# 2_ADC.net
KiCad netlist of a schematic drawn in Altium Designer
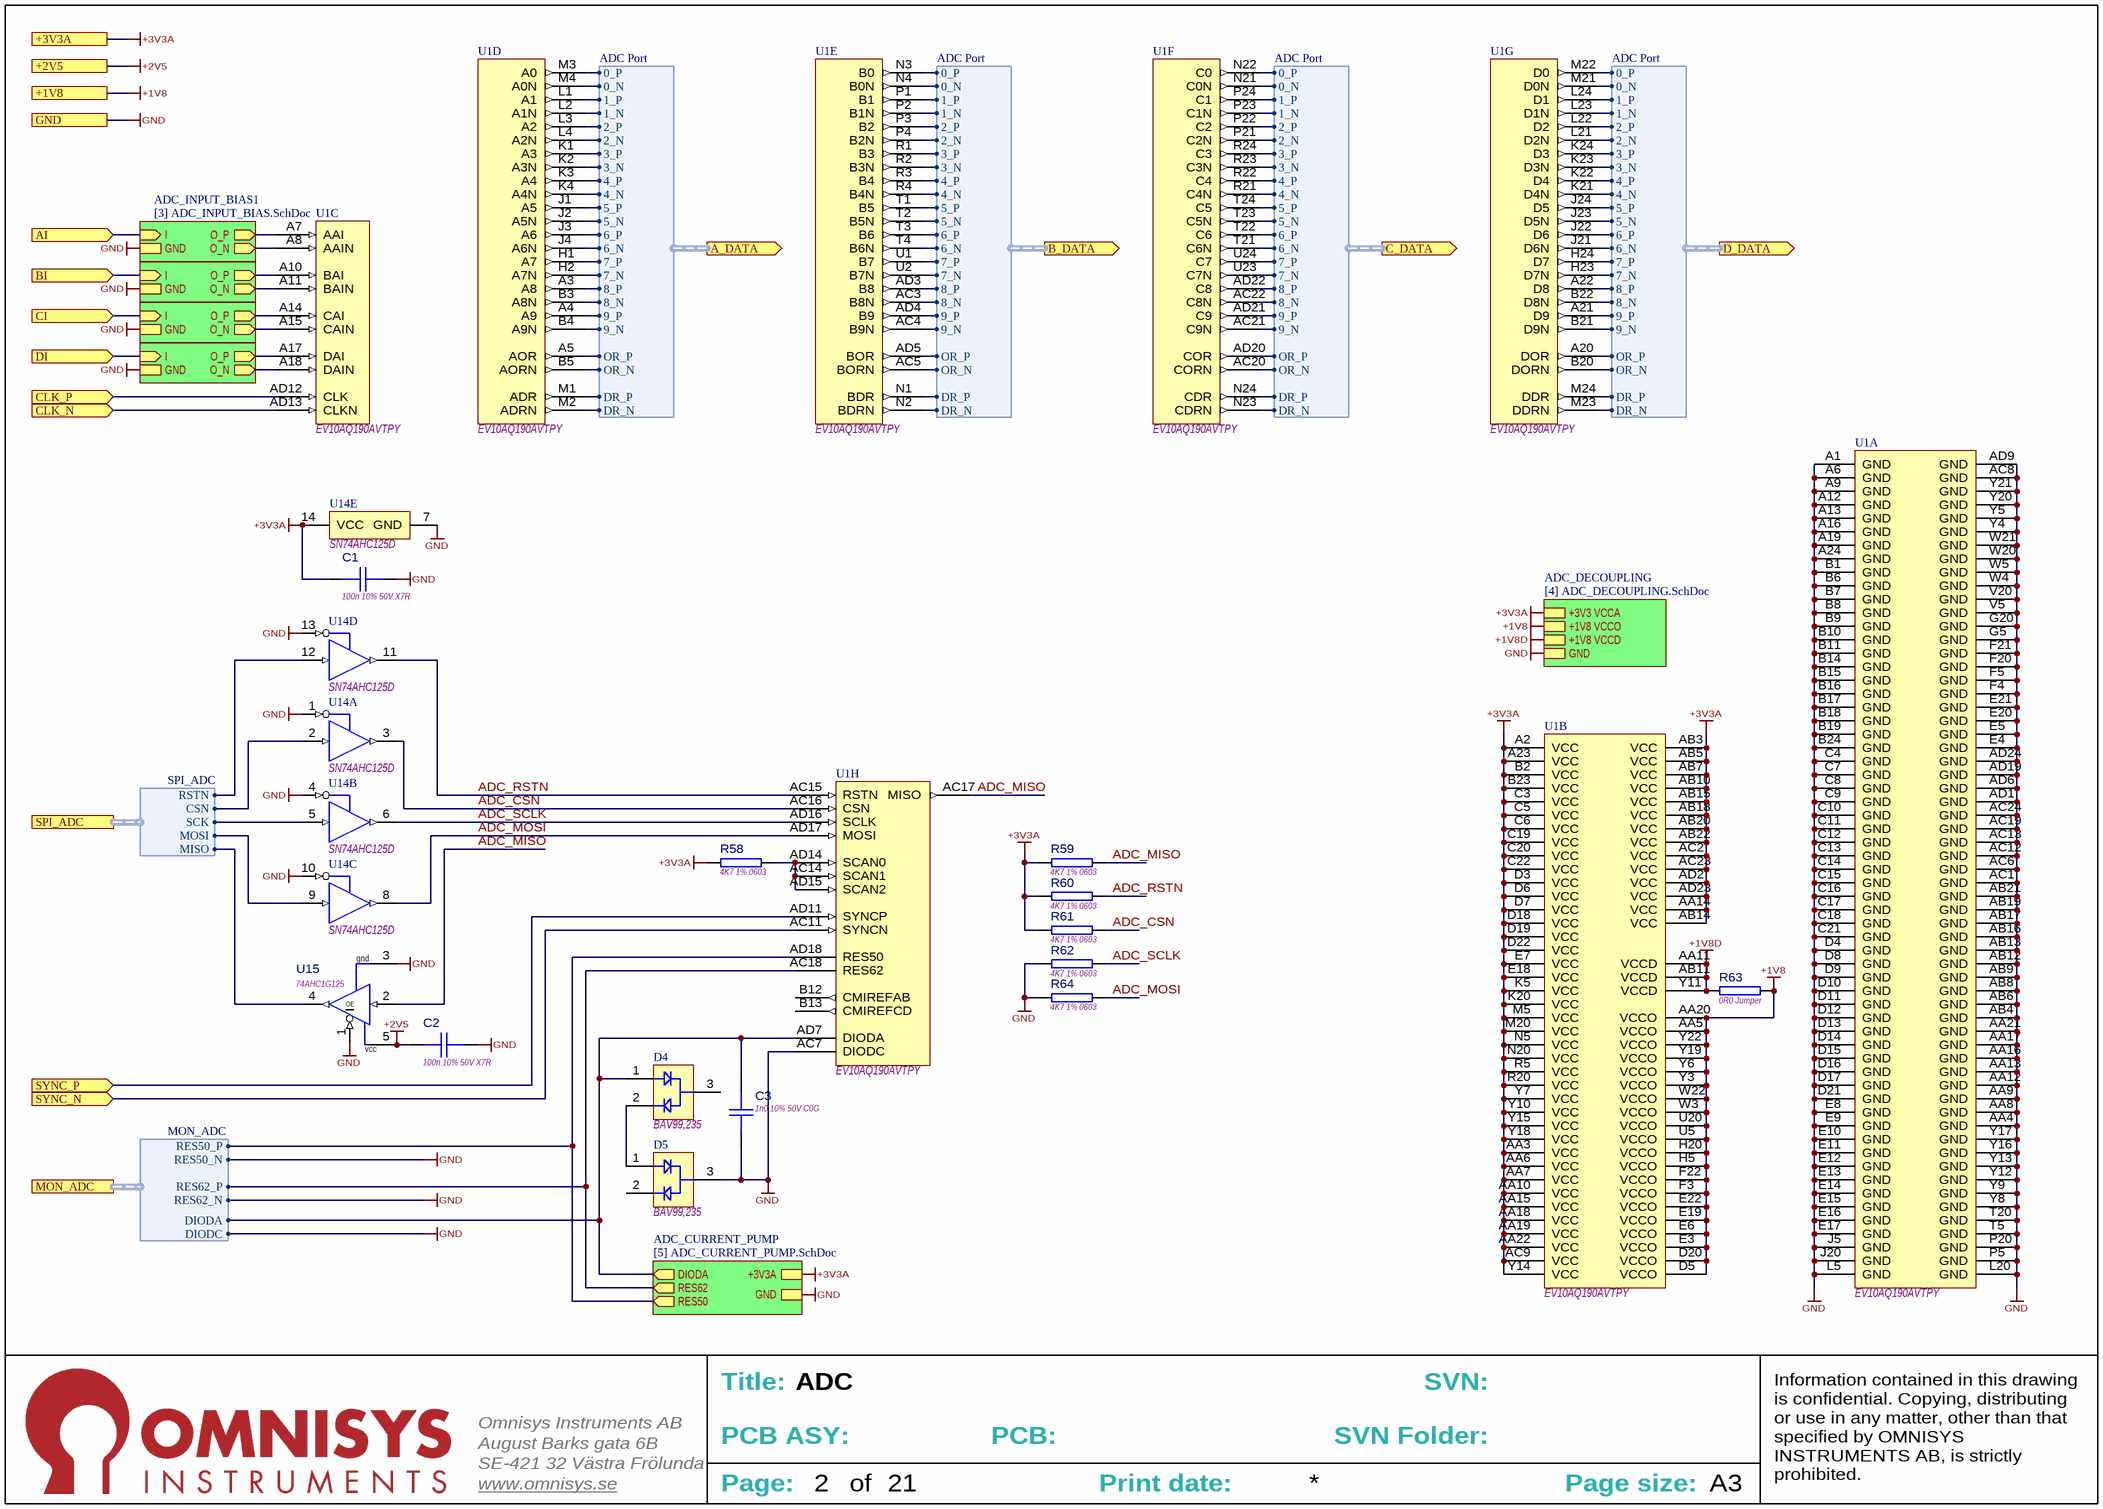
[diagram p0: [2] ADC.SchDoc]

(export (version "E")
  (design (tool "Eeschema 10.0.6"))
  (components
    (comp (ref "C1")
      (value "100n 10% 50V X7R")
      (footprint "CAPC1608X90N")
      (description "Ceramic Chip Capacitor, 0603/1608")
      (fields (field (name "TOLERANCE") "10%"))
      (libsource (lib "Omnisys Vault") (part "CAP-2PIN"))
    )
    (comp (ref "C2")
      (value "100n 10% 50V X7R")
      (footprint "CAPC1608X90N")
      (description "Ceramic Chip Capacitor, 0603/1608")
      (fields (field (name "TOLERANCE") "10%"))
      (libsource (lib "Omnisys Vault") (part "CAP-2PIN"))
    )
    (comp (ref "C3")
      (value "1n0 10% 50V C0G")
      (footprint "CAPC1608X90N")
      (description "Ceramic Chip Capacitor, 0603/1608")
      (fields (field (name "TOLERANCE") "5%"))
      (libsource (lib "Omnisys Vault") (part "CAP-2PIN"))
    )
    (comp (ref "D4")
      (value "BAV99,235")
      (footprint "SOT95P230X110-3N")
      (description "BAV99 Series 100 V 215 mA SMT High Speed Switching Diode - SOT-23")
      (fields (field (name "VOLTAGE") "75V"))
      (libsource (lib "Omnisys Vault") (part "INF-D_A1K2C3-3"))
    )
    (comp (ref "D5")
      (value "BAV99,235")
      (footprint "SOT95P230X110-3N")
      (description "BAV99 Series 100 V 215 mA SMT High Speed Switching Diode - SOT-23")
      (fields (field (name "VOLTAGE") "75V"))
      (libsource (lib "Omnisys Vault") (part "INF-D_A1K2C3-3"))
    )
    (comp (ref "R58")
      (value "4K7 1% 0603")
      (footprint "RESC1608N")
      (description "Thick film Chip Resistor, 0603/1608")
      (fields (field (name "POWER") "100mW") (field (name "TOLERANCE") "1%"))
      (libsource (lib "Omnisys Vault") (part "RES-2PIN"))
    )
    (comp (ref "R59")
      (value "4K7 1% 0603")
      (footprint "RESC1608N")
      (description "Thick film Chip Resistor, 0603/1608")
      (fields (field (name "POWER") "100mW") (field (name "TOLERANCE") "1%"))
      (libsource (lib "Omnisys Vault") (part "RES-2PIN"))
    )
    (comp (ref "R60")
      (value "4K7 1% 0603")
      (footprint "RESC1608N")
      (description "Thick film Chip Resistor, 0603/1608")
      (fields (field (name "POWER") "100mW") (field (name "TOLERANCE") "1%"))
      (libsource (lib "Omnisys Vault") (part "RES-2PIN"))
    )
    (comp (ref "R61")
      (value "4K7 1% 0603")
      (footprint "RESC1608N")
      (description "Thick film Chip Resistor, 0603/1608")
      (fields (field (name "POWER") "100mW") (field (name "TOLERANCE") "1%"))
      (libsource (lib "Omnisys Vault") (part "RES-2PIN"))
    )
    (comp (ref "R62")
      (value "4K7 1% 0603")
      (footprint "RESC1608N")
      (description "Thick film Chip Resistor, 0603/1608")
      (fields (field (name "POWER") "100mW") (field (name "TOLERANCE") "1%"))
      (libsource (lib "Omnisys Vault") (part "RES-2PIN"))
    )
    (comp (ref "R63")
      (value "0R0 Jumper")
      (footprint "RESC2012N")
      (description "Thick film Chip Resistor, 0805/2012")
      (fields (field (name "POWER") "0W") (field (name "TOLERANCE") "0%"))
      (libsource (lib "Omnisys Vault") (part "RES-2PIN"))
    )
    (comp (ref "R64")
      (value "4K7 1% 0603")
      (footprint "RESC1608N")
      (description "Thick film Chip Resistor, 0603/1608")
      (fields (field (name "POWER") "100mW") (field (name "TOLERANCE") "1%"))
      (libsource (lib "Omnisys Vault") (part "RES-2PIN"))
    )
    (comp (ref "U1")
      (value "EV10AQ190AVTPY")
      (footprint "BGA380C127P24X24_3100X3100X160")
      (description "Quad ADC 1.25Gsps 10-bit Parallel/LVDS 380-Pin EBGA")
      (libsource (lib "Omnisys Vault") (part "EV10AQ190AVTPY"))
    )
    (comp (ref "U14")
      (value "SN74AHC125D")
      (footprint "SOIC127P600X175-14N")
      (description "Buffer/Line Driver 4-CH Non-Inverting 3-ST CMOS 14-Pin SOIC Tube")
      (libsource (lib "Omnisys Vault") (part "SN74AHC125D"))
    )
    (comp (ref "U15")
      (value "74AHC1G125")
      (footprint "SOT95P280X100-5N")
      (description "Single bus buffer gate with 3-state output")
      (libsource (lib "Omnisys Vault") (part "74AHC1G125"))
    )
  )
  (nets
    (net (code "5") (name "+1V8") (class "Default")
      (node (ref "R63") (pin "2") (pinfunction "2_2") (pintype "passive"))
      (node (ref "U1") (pin "AA20") (pinfunction "VCCO_AA20") (pintype "power_in"))
      (node (ref "U1") (pin "AA5") (pinfunction "VCCO_AA5") (pintype "power_in"))
      (node (ref "U1") (pin "D20") (pinfunction "VCCO_D20") (pintype "power_in"))
      (node (ref "U1") (pin "D5") (pinfunction "VCCO_D5") (pintype "power_in"))
      (node (ref "U1") (pin "E19") (pinfunction "VCCO_E19") (pintype "power_in"))
      (node (ref "U1") (pin "E22") (pinfunction "VCCO_E22") (pintype "power_in"))
      (node (ref "U1") (pin "E3") (pinfunction "VCCO_E3") (pintype "power_in"))
      (node (ref "U1") (pin "E6") (pinfunction "VCCO_E6") (pintype "power_in"))
      (node (ref "U1") (pin "F22") (pinfunction "VCCO_F22") (pintype "power_in"))
      (node (ref "U1") (pin "F3") (pinfunction "VCCO_F3") (pintype "power_in"))
      (node (ref "U1") (pin "H20") (pinfunction "VCCO_H20") (pintype "power_in"))
      (node (ref "U1") (pin "H5") (pinfunction "VCCO_H5") (pintype "power_in"))
      (node (ref "U1") (pin "U20") (pinfunction "VCCO_U20") (pintype "power_in"))
      (node (ref "U1") (pin "U5") (pinfunction "VCCO_U5") (pintype "power_in"))
      (node (ref "U1") (pin "W22") (pinfunction "VCCO_W22") (pintype "power_in"))
      (node (ref "U1") (pin "W3") (pinfunction "VCCO_W3") (pintype "power_in"))
      (node (ref "U1") (pin "Y19") (pinfunction "VCCO_Y19") (pintype "power_in"))
      (node (ref "U1") (pin "Y22") (pinfunction "VCCO_Y22") (pintype "power_in"))
      (node (ref "U1") (pin "Y3") (pinfunction "VCCO_Y3") (pintype "power_in"))
      (node (ref "U1") (pin "Y6") (pinfunction "VCCO_Y6") (pintype "power_in"))
    )
    (net (code "6") (name "+1V8D") (class "Default")
      (node (ref "R63") (pin "1") (pinfunction "1_1") (pintype "passive"))
      (node (ref "U1") (pin "AA11") (pinfunction "VCCD_AA11") (pintype "power_in"))
      (node (ref "U1") (pin "AB11") (pinfunction "VCCD_AB11") (pintype "power_in"))
      (node (ref "U1") (pin "Y11") (pinfunction "VCCD_Y11") (pintype "power_in"))
    )
    (net (code "7") (name "+2V5") (class "Default")
      (node (ref "C2") (pin "1") (pinfunction "1_1") (pintype "passive"))
      (node (ref "U15") (pin "5") (pinfunction "VCC_5") (pintype "power_in"))
    )
    (net (code "8") (name "+3V3A") (class "Default")
      (node (ref "C1") (pin "1") (pinfunction "1_1") (pintype "passive"))
      (node (ref "R58") (pin "2") (pinfunction "2_2") (pintype "passive"))
      (node (ref "R59") (pin "2") (pinfunction "2_2") (pintype "passive"))
      (node (ref "R60") (pin "1") (pinfunction "1_1") (pintype "passive"))
      (node (ref "R61") (pin "1") (pinfunction "1_1") (pintype "passive"))
      (node (ref "U1") (pin "A2") (pinfunction "VCC_A2") (pintype "power_in"))
      (node (ref "U1") (pin "A23") (pinfunction "VCC_A23") (pintype "power_in"))
      (node (ref "U1") (pin "AA10") (pinfunction "VCC_AA10") (pintype "power_in"))
      (node (ref "U1") (pin "AA14") (pinfunction "VCC_AA14") (pintype "power_in"))
      (node (ref "U1") (pin "AA15") (pinfunction "VCC_AA15") (pintype "power_in"))
      (node (ref "U1") (pin "AA18") (pinfunction "VCC_AA18") (pintype "power_in"))
      (node (ref "U1") (pin "AA19") (pinfunction "VCC_AA19") (pintype "power_in"))
      (node (ref "U1") (pin "AA22") (pinfunction "VCC_AA22") (pintype "power_in"))
      (node (ref "U1") (pin "AA3") (pinfunction "VCC_AA3") (pintype "power_in"))
      (node (ref "U1") (pin "AA6") (pinfunction "VCC_AA6") (pintype "power_in"))
      (node (ref "U1") (pin "AA7") (pinfunction "VCC_AA7") (pintype "power_in"))
      (node (ref "U1") (pin "AB10") (pinfunction "VCC_AB10") (pintype "power_in"))
      (node (ref "U1") (pin "AB14") (pinfunction "VCC_AB14") (pintype "power_in"))
      (node (ref "U1") (pin "AB15") (pinfunction "VCC_AB15") (pintype "power_in"))
      (node (ref "U1") (pin "AB18") (pinfunction "VCC_AB18") (pintype "power_in"))
      (node (ref "U1") (pin "AB20") (pinfunction "VCC_AB20") (pintype "power_in"))
      (node (ref "U1") (pin "AB22") (pinfunction "VCC_AB22") (pintype "power_in"))
      (node (ref "U1") (pin "AB3") (pinfunction "VCC_AB3") (pintype "power_in"))
      (node (ref "U1") (pin "AB5") (pinfunction "VCC_AB5") (pintype "power_in"))
      (node (ref "U1") (pin "AB7") (pinfunction "VCC_AB7") (pintype "power_in"))
      (node (ref "U1") (pin "AC2") (pinfunction "VCC_AC2") (pintype "power_in"))
      (node (ref "U1") (pin "AC23") (pinfunction "VCC_AC23") (pintype "power_in"))
      (node (ref "U1") (pin "AC9") (pinfunction "VCC_AC9") (pintype "power_in"))
      (node (ref "U1") (pin "AD2") (pinfunction "VCC_AD2") (pintype "power_in"))
      (node (ref "U1") (pin "AD23") (pinfunction "VCC_AD23") (pintype "power_in"))
      (node (ref "U1") (pin "B2") (pinfunction "VCC_B2") (pintype "power_in"))
      (node (ref "U1") (pin "B23") (pinfunction "VCC_B23") (pintype "power_in"))
      (node (ref "U1") (pin "C19") (pinfunction "VCC_C19") (pintype "power_in"))
      (node (ref "U1") (pin "C20") (pinfunction "VCC_C20") (pintype "power_in"))
      (node (ref "U1") (pin "C22") (pinfunction "VCC_C22") (pintype "power_in"))
      (node (ref "U1") (pin "C3") (pinfunction "VCC_C3") (pintype "power_in"))
      (node (ref "U1") (pin "C5") (pinfunction "VCC_C5") (pintype "power_in"))
      (node (ref "U1") (pin "C6") (pinfunction "VCC_C6") (pintype "power_in"))
      (node (ref "U1") (pin "D18") (pinfunction "VCC_D18") (pintype "power_in"))
      (node (ref "U1") (pin "D19") (pinfunction "VCC_D19") (pintype "power_in"))
      (node (ref "U1") (pin "D22") (pinfunction "VCC_D22") (pintype "power_in"))
      (node (ref "U1") (pin "D3") (pinfunction "VCC_D3") (pintype "power_in"))
      (node (ref "U1") (pin "D6") (pinfunction "VCC_D6") (pintype "power_in"))
      (node (ref "U1") (pin "D7") (pinfunction "VCC_D7") (pintype "power_in"))
      (node (ref "U1") (pin "E18") (pinfunction "VCC_E18") (pintype "power_in"))
      (node (ref "U1") (pin "E7") (pinfunction "VCC_E7") (pintype "power_in"))
      (node (ref "U1") (pin "K20") (pinfunction "VCC_K20") (pintype "power_in"))
      (node (ref "U1") (pin "K5") (pinfunction "VCC_K5") (pintype "power_in"))
      (node (ref "U1") (pin "M20") (pinfunction "VCC_M20") (pintype "power_in"))
      (node (ref "U1") (pin "M5") (pinfunction "VCC_M5") (pintype "power_in"))
      (node (ref "U1") (pin "N20") (pinfunction "VCC_N20") (pintype "power_in"))
      (node (ref "U1") (pin "N5") (pinfunction "VCC_N5") (pintype "power_in"))
      (node (ref "U1") (pin "R20") (pinfunction "VCC_R20") (pintype "power_in"))
      (node (ref "U1") (pin "R5") (pinfunction "VCC_R5") (pintype "power_in"))
      (node (ref "U1") (pin "Y10") (pinfunction "VCC_Y10") (pintype "power_in"))
      (node (ref "U1") (pin "Y14") (pinfunction "VCC_Y14") (pintype "power_in"))
      (node (ref "U1") (pin "Y15") (pinfunction "VCC_Y15") (pintype "power_in"))
      (node (ref "U1") (pin "Y18") (pinfunction "VCC_Y18") (pintype "power_in"))
      (node (ref "U1") (pin "Y7") (pinfunction "VCC_Y7") (pintype "power_in"))
      (node (ref "U14") (pin "14") (pinfunction "VCC_14") (pintype "power_in"))
    )
    (net (code "9") (name "/ADC_CSN") (class "Default")
      (node (ref "R61") (pin "2") (pinfunction "2_2") (pintype "passive"))
      (node (ref "U1") (pin "AC16") (pinfunction "CSN_AC16") (pintype "input"))
      (node (ref "U14") (pin "3") (pinfunction "1Y_3") (pintype "output"))
    )
    (net (code "10") (name "/ADC_MISO") (class "Default")
      (node (ref "R59") (pin "1") (pinfunction "1_1") (pintype "passive"))
      (node (ref "U1") (pin "AC17") (pinfunction "MISO_AC17") (pintype "output"))
      (node (ref "U15") (pin "2") (pinfunction "B_2") (pintype "input"))
    )
    (net (code "11") (name "/ADC_MOSI") (class "Default")
      (node (ref "R64") (pin "2") (pinfunction "2_2") (pintype "passive"))
      (node (ref "U1") (pin "AD17") (pinfunction "MOSI_AD17") (pintype "input"))
      (node (ref "U14") (pin "8") (pinfunction "3Y_8") (pintype "output"))
    )
    (net (code "12") (name "/ADC_RSTN") (class "Default")
      (node (ref "R60") (pin "2") (pinfunction "2_2") (pintype "passive"))
      (node (ref "U1") (pin "AC15") (pinfunction "RSTN_AC15") (pintype "input"))
      (node (ref "U14") (pin "11") (pinfunction "4Y_11") (pintype "output"))
    )
    (net (code "13") (name "/ADC_SCLK") (class "Default")
      (node (ref "R62") (pin "2") (pinfunction "2_2") (pintype "passive"))
      (node (ref "U1") (pin "AD16") (pinfunction "SCLK_AD16") (pintype "input"))
      (node (ref "U14") (pin "6") (pinfunction "2Y_6") (pintype "output"))
    )
    (net (code "17") (name "/CLK_N") (class "Default")
      (node (ref "U1") (pin "AD13") (pinfunction "CLKN_AD13") (pintype "input"))
    )
    (net (code "18") (name "/CLK_P") (class "Default")
      (node (ref "U1") (pin "AD12") (pinfunction "CLK_AD12") (pintype "input"))
    )
    (net (code "20") (name "/DIODA") (class "Default")
      (node (ref "C3") (pin "2") (pinfunction "2_2") (pintype "passive"))
      (node (ref "D4") (pin "1") (pinfunction "A1_1") (pintype "passive"))
      (node (ref "U1") (pin "AD7") (pinfunction "DIODA_AD7") (pintype "passive"))
    )
    (net (code "21") (name "/O_N") (class "Default")
      (node (ref "U1") (pin "A18") (pinfunction "DAIN_A18") (pintype "input"))
    )
    (net (code "22") (name "/O_N_1") (class "Default")
      (node (ref "U1") (pin "A8") (pinfunction "AAIN_A8") (pintype "input"))
    )
    (net (code "23") (name "/O_N_2") (class "Default")
      (node (ref "U1") (pin "A11") (pinfunction "BAIN_A11") (pintype "input"))
    )
    (net (code "24") (name "/O_N_3") (class "Default")
      (node (ref "U1") (pin "A15") (pinfunction "CAIN_A15") (pintype "input"))
    )
    (net (code "25") (name "/O_P") (class "Default")
      (node (ref "U1") (pin "A17") (pinfunction "DAI_A17") (pintype "input"))
    )
    (net (code "26") (name "/O_P_1") (class "Default")
      (node (ref "U1") (pin "A7") (pinfunction "AAI_A7") (pintype "input"))
    )
    (net (code "27") (name "/O_P_2") (class "Default")
      (node (ref "U1") (pin "A10") (pinfunction "BAI_A10") (pintype "input"))
    )
    (net (code "28") (name "/O_P_3") (class "Default")
      (node (ref "U1") (pin "A14") (pinfunction "CAI_A14") (pintype "input"))
    )
    (net (code "29") (name "/RES50") (class "Default")
      (node (ref "U1") (pin "AD18") (pinfunction "RES50_AD18") (pintype "passive"))
    )
    (net (code "30") (name "/RES62") (class "Default")
      (node (ref "U1") (pin "AC18") (pinfunction "RES62_AC18") (pintype "passive"))
    )
    (net (code "31") (name "/SYNC_N") (class "Default")
      (node (ref "U1") (pin "AC11") (pinfunction "SYNCN_AC11") (pintype "input"))
    )
    (net (code "32") (name "/SYNC_P") (class "Default")
      (node (ref "U1") (pin "AD11") (pinfunction "SYNCP_AD11") (pintype "input"))
    )
    (net (code "36") (name "GND") (class "Default")
      (node (ref "C1") (pin "2") (pinfunction "2_2") (pintype "passive"))
      (node (ref "C2") (pin "2") (pinfunction "2_2") (pintype "passive"))
      (node (ref "C3") (pin "1") (pinfunction "1_1") (pintype "passive"))
      (node (ref "D5") (pin "3") (pinfunction "C_3") (pintype "passive"))
      (node (ref "R62") (pin "1") (pinfunction "1_1") (pintype "passive"))
      (node (ref "R64") (pin "1") (pinfunction "1_1") (pintype "passive"))
      (node (ref "U1") (pin "A1") (pinfunction "GND_A1") (pintype "power_in"))
      (node (ref "U1") (pin "A12") (pinfunction "GND_A12") (pintype "power_in"))
      (node (ref "U1") (pin "A13") (pinfunction "GND_A13") (pintype "power_in"))
      (node (ref "U1") (pin "A16") (pinfunction "GND_A16") (pintype "power_in"))
      (node (ref "U1") (pin "A19") (pinfunction "GND_A19") (pintype "power_in"))
      (node (ref "U1") (pin "A24") (pinfunction "GND_A24") (pintype "power_in"))
      (node (ref "U1") (pin "A6") (pinfunction "GND_A6") (pintype "power_in"))
      (node (ref "U1") (pin "A9") (pinfunction "GND_A9") (pintype "power_in"))
      (node (ref "U1") (pin "AA12") (pinfunction "GND_AA12") (pintype "power_in"))
      (node (ref "U1") (pin "AA13") (pinfunction "GND_AA13") (pintype "power_in"))
      (node (ref "U1") (pin "AA16") (pinfunction "GND_AA16") (pintype "power_in"))
      (node (ref "U1") (pin "AA17") (pinfunction "GND_AA17") (pintype "power_in"))
      (node (ref "U1") (pin "AA21") (pinfunction "GND_AA21") (pintype "power_in"))
      (node (ref "U1") (pin "AA4") (pinfunction "GND_AA4") (pintype "power_in"))
      (node (ref "U1") (pin "AA8") (pinfunction "GND_AA8") (pintype "power_in"))
      (node (ref "U1") (pin "AA9") (pinfunction "GND_AA9") (pintype "power_in"))
      (node (ref "U1") (pin "AB12") (pinfunction "GND_AB12") (pintype "power_in"))
      (node (ref "U1") (pin "AB13") (pinfunction "GND_AB13") (pintype "power_in"))
      (node (ref "U1") (pin "AB16") (pinfunction "GND_AB16") (pintype "power_in"))
      (node (ref "U1") (pin "AB17") (pinfunction "GND_AB17") (pintype "power_in"))
      (node (ref "U1") (pin "AB19") (pinfunction "GND_AB19") (pintype "power_in"))
      (node (ref "U1") (pin "AB21") (pinfunction "GND_AB21") (pintype "power_in"))
      (node (ref "U1") (pin "AB4") (pinfunction "GND_AB4") (pintype "power_in"))
      (node (ref "U1") (pin "AB6") (pinfunction "GND_AB6") (pintype "power_in"))
      (node (ref "U1") (pin "AB8") (pinfunction "GND_AB8") (pintype "power_in"))
      (node (ref "U1") (pin "AB9") (pinfunction "GND_AB9") (pintype "power_in"))
      (node (ref "U1") (pin "AC1") (pinfunction "GND_AC1") (pintype "power_in"))
      (node (ref "U1") (pin "AC12") (pinfunction "GND_AC12") (pintype "power_in"))
      (node (ref "U1") (pin "AC13") (pinfunction "GND_AC13") (pintype "power_in"))
      (node (ref "U1") (pin "AC19") (pinfunction "GND_AC19") (pintype "power_in"))
      (node (ref "U1") (pin "AC24") (pinfunction "GND_AC24") (pintype "power_in"))
      (node (ref "U1") (pin "AC6") (pinfunction "GND_AC6") (pintype "power_in"))
      (node (ref "U1") (pin "AC7") (pinfunction "DIODC_AC7") (pintype "passive"))
      (node (ref "U1") (pin "AC8") (pinfunction "GND_AC8") (pintype "power_in"))
      (node (ref "U1") (pin "AD1") (pinfunction "GND_AD1") (pintype "power_in"))
      (node (ref "U1") (pin "AD19") (pinfunction "GND_AD19") (pintype "power_in"))
      (node (ref "U1") (pin "AD24") (pinfunction "GND_AD24") (pintype "power_in"))
      (node (ref "U1") (pin "AD6") (pinfunction "GND_AD6") (pintype "power_in"))
      (node (ref "U1") (pin "AD9") (pinfunction "GND_AD9") (pintype "power_in"))
      (node (ref "U1") (pin "B1") (pinfunction "GND_B1") (pintype "power_in"))
      (node (ref "U1") (pin "B10") (pinfunction "GND_B10") (pintype "power_in"))
      (node (ref "U1") (pin "B11") (pinfunction "GND_B11") (pintype "power_in"))
      (node (ref "U1") (pin "B14") (pinfunction "GND_B14") (pintype "power_in"))
      (node (ref "U1") (pin "B15") (pinfunction "GND_B15") (pintype "power_in"))
      (node (ref "U1") (pin "B16") (pinfunction "GND_B16") (pintype "power_in"))
      (node (ref "U1") (pin "B17") (pinfunction "GND_B17") (pintype "power_in"))
      (node (ref "U1") (pin "B18") (pinfunction "GND_B18") (pintype "power_in"))
      (node (ref "U1") (pin "B19") (pinfunction "GND_B19") (pintype "power_in"))
      (node (ref "U1") (pin "B24") (pinfunction "GND_B24") (pintype "power_in"))
      (node (ref "U1") (pin "B6") (pinfunction "GND_B6") (pintype "power_in"))
      (node (ref "U1") (pin "B7") (pinfunction "GND_B7") (pintype "power_in"))
      (node (ref "U1") (pin "B8") (pinfunction "GND_B8") (pintype "power_in"))
      (node (ref "U1") (pin "B9") (pinfunction "GND_B9") (pintype "power_in"))
      (node (ref "U1") (pin "C10") (pinfunction "GND_C10") (pintype "power_in"))
      (node (ref "U1") (pin "C11") (pinfunction "GND_C11") (pintype "power_in"))
      (node (ref "U1") (pin "C12") (pinfunction "GND_C12") (pintype "power_in"))
      (node (ref "U1") (pin "C13") (pinfunction "GND_C13") (pintype "power_in"))
      (node (ref "U1") (pin "C14") (pinfunction "GND_C14") (pintype "power_in"))
      (node (ref "U1") (pin "C15") (pinfunction "GND_C15") (pintype "power_in"))
      (node (ref "U1") (pin "C16") (pinfunction "GND_C16") (pintype "power_in"))
      (node (ref "U1") (pin "C17") (pinfunction "GND_C17") (pintype "power_in"))
      (node (ref "U1") (pin "C18") (pinfunction "GND_C18") (pintype "power_in"))
      (node (ref "U1") (pin "C21") (pinfunction "GND_C21") (pintype "power_in"))
      (node (ref "U1") (pin "C4") (pinfunction "GND_C4") (pintype "power_in"))
      (node (ref "U1") (pin "C7") (pinfunction "GND_C7") (pintype "power_in"))
      (node (ref "U1") (pin "C8") (pinfunction "GND_C8") (pintype "power_in"))
      (node (ref "U1") (pin "C9") (pinfunction "GND_C9") (pintype "power_in"))
      (node (ref "U1") (pin "D10") (pinfunction "GND_D10") (pintype "power_in"))
      (node (ref "U1") (pin "D11") (pinfunction "GND_D11") (pintype "power_in"))
      (node (ref "U1") (pin "D12") (pinfunction "GND_D12") (pintype "power_in"))
      (node (ref "U1") (pin "D13") (pinfunction "GND_D13") (pintype "power_in"))
      (node (ref "U1") (pin "D14") (pinfunction "GND_D14") (pintype "power_in"))
      (node (ref "U1") (pin "D15") (pinfunction "GND_D15") (pintype "power_in"))
      (node (ref "U1") (pin "D16") (pinfunction "GND_D16") (pintype "power_in"))
      (node (ref "U1") (pin "D17") (pinfunction "GND_D17") (pintype "power_in"))
      (node (ref "U1") (pin "D21") (pinfunction "GND_D21") (pintype "power_in"))
      (node (ref "U1") (pin "D4") (pinfunction "GND_D4") (pintype "power_in"))
      (node (ref "U1") (pin "D8") (pinfunction "GND_D8") (pintype "power_in"))
      (node (ref "U1") (pin "D9") (pinfunction "GND_D9") (pintype "power_in"))
      (node (ref "U1") (pin "E10") (pinfunction "GND_E10") (pintype "power_in"))
      (node (ref "U1") (pin "E11") (pinfunction "GND_E11") (pintype "power_in"))
      (node (ref "U1") (pin "E12") (pinfunction "GND_E12") (pintype "power_in"))
      (node (ref "U1") (pin "E13") (pinfunction "GND_E13") (pintype "power_in"))
      (node (ref "U1") (pin "E14") (pinfunction "GND_E14") (pintype "power_in"))
      (node (ref "U1") (pin "E15") (pinfunction "GND_E15") (pintype "power_in"))
      (node (ref "U1") (pin "E16") (pinfunction "GND_E16") (pintype "power_in"))
      (node (ref "U1") (pin "E17") (pinfunction "GND_E17") (pintype "power_in"))
      (node (ref "U1") (pin "E20") (pinfunction "GND_E20") (pintype "power_in"))
      (node (ref "U1") (pin "E21") (pinfunction "GND_E21") (pintype "power_in"))
      (node (ref "U1") (pin "E4") (pinfunction "GND_E4") (pintype "power_in"))
      (node (ref "U1") (pin "E5") (pinfunction "GND_E5") (pintype "power_in"))
      (node (ref "U1") (pin "E8") (pinfunction "GND_E8") (pintype "power_in"))
      (node (ref "U1") (pin "E9") (pinfunction "GND_E9") (pintype "power_in"))
      (node (ref "U1") (pin "F20") (pinfunction "GND_F20") (pintype "power_in"))
      (node (ref "U1") (pin "F21") (pinfunction "GND_F21") (pintype "power_in"))
      (node (ref "U1") (pin "F4") (pinfunction "GND_F4") (pintype "power_in"))
      (node (ref "U1") (pin "F5") (pinfunction "GND_F5") (pintype "power_in"))
      (node (ref "U1") (pin "G20") (pinfunction "GND_G20") (pintype "power_in"))
      (node (ref "U1") (pin "G5") (pinfunction "GND_G5") (pintype "power_in"))
      (node (ref "U1") (pin "J20") (pinfunction "GND_J20") (pintype "power_in"))
      (node (ref "U1") (pin "J5") (pinfunction "GND_J5") (pintype "power_in"))
      (node (ref "U1") (pin "L20") (pinfunction "GND_L20") (pintype "power_in"))
      (node (ref "U1") (pin "L5") (pinfunction "GND_L5") (pintype "power_in"))
      (node (ref "U1") (pin "P20") (pinfunction "GND_P20") (pintype "power_in"))
      (node (ref "U1") (pin "P5") (pinfunction "GND_P5") (pintype "power_in"))
      (node (ref "U1") (pin "T20") (pinfunction "GND_T20") (pintype "power_in"))
      (node (ref "U1") (pin "T5") (pinfunction "GND_T5") (pintype "power_in"))
      (node (ref "U1") (pin "V20") (pinfunction "GND_V20") (pintype "power_in"))
      (node (ref "U1") (pin "V5") (pinfunction "GND_V5") (pintype "power_in"))
      (node (ref "U1") (pin "W20") (pinfunction "GND_W20") (pintype "power_in"))
      (node (ref "U1") (pin "W21") (pinfunction "GND_W21") (pintype "power_in"))
      (node (ref "U1") (pin "W4") (pinfunction "GND_W4") (pintype "power_in"))
      (node (ref "U1") (pin "W5") (pinfunction "GND_W5") (pintype "power_in"))
      (node (ref "U1") (pin "Y12") (pinfunction "GND_Y12") (pintype "power_in"))
      (node (ref "U1") (pin "Y13") (pinfunction "GND_Y13") (pintype "power_in"))
      (node (ref "U1") (pin "Y16") (pinfunction "GND_Y16") (pintype "power_in"))
      (node (ref "U1") (pin "Y17") (pinfunction "GND_Y17") (pintype "power_in"))
      (node (ref "U1") (pin "Y20") (pinfunction "GND_Y20") (pintype "power_in"))
      (node (ref "U1") (pin "Y21") (pinfunction "GND_Y21") (pintype "power_in"))
      (node (ref "U1") (pin "Y4") (pinfunction "GND_Y4") (pintype "power_in"))
      (node (ref "U1") (pin "Y5") (pinfunction "GND_Y5") (pintype "power_in"))
      (node (ref "U1") (pin "Y8") (pinfunction "GND_Y8") (pintype "power_in"))
      (node (ref "U1") (pin "Y9") (pinfunction "GND_Y9") (pintype "power_in"))
      (node (ref "U14") (pin "1") (pinfunction "1OE#_1") (pintype "input"))
      (node (ref "U14") (pin "10") (pinfunction "3OE#_10") (pintype "input"))
      (node (ref "U14") (pin "13") (pinfunction "4OE#_13") (pintype "input"))
      (node (ref "U14") (pin "4") (pinfunction "2OE#_4") (pintype "input"))
      (node (ref "U14") (pin "7") (pinfunction "GND_7") (pintype "power_in"))
      (node (ref "U15") (pin "1") (pinfunction "~{O}E_1") (pintype "input"))
      (node (ref "U15") (pin "3") (pinfunction "GND_3") (pintype "power_in"))
    )
    (net (code "37") (name "Net-(D4-K2)") (class "Default")
      (node (ref "D4") (pin "2") (pinfunction "K2_2") (pintype "passive"))
      (node (ref "D5") (pin "1") (pinfunction "A1_1") (pintype "passive"))
    )
    (net (code "38") (name "Net-(U1H-SCAN0)") (class "Default")
      (node (ref "R58") (pin "1") (pinfunction "1_1") (pintype "passive"))
      (node (ref "U1") (pin "AC14") (pinfunction "SCAN1_AC14") (pintype "input"))
      (node (ref "U1") (pin "AD14") (pinfunction "SCAN0_AD14") (pintype "input"))
      (node (ref "U1") (pin "AD15") (pinfunction "SCAN2_AD15") (pintype "input"))
    )
    (net (code "39") (name "unconnected-(D4-C-Pad3)") (class "Default")
      (node (ref "D4") (pin "3") (pinfunction "C_3") (pintype "passive"))
    )
    (net (code "40") (name "unconnected-(D5-K2-Pad2)") (class "Default")
      (node (ref "D5") (pin "2") (pinfunction "K2_2") (pintype "passive"))
    )
    (net (code "41") (name "unconnected-(U1D-A0-PadM3)") (class "Default")
      (node (ref "U1") (pin "M3") (pinfunction "A0_M3") (pintype "output"))
    )
    (net (code "42") (name "unconnected-(U1D-A0N-PadM4)") (class "Default")
      (node (ref "U1") (pin "M4") (pinfunction "A0N_M4") (pintype "output"))
    )
    (net (code "43") (name "unconnected-(U1D-A1-PadL1)") (class "Default")
      (node (ref "U1") (pin "L1") (pinfunction "A1_L1") (pintype "output"))
    )
    (net (code "44") (name "unconnected-(U1D-A1N-PadL2)") (class "Default")
      (node (ref "U1") (pin "L2") (pinfunction "A1N_L2") (pintype "output"))
    )
    (net (code "45") (name "unconnected-(U1D-A2-PadL3)") (class "Default")
      (node (ref "U1") (pin "L3") (pinfunction "A2_L3") (pintype "output"))
    )
    (net (code "46") (name "unconnected-(U1D-A2N-PadL4)") (class "Default")
      (node (ref "U1") (pin "L4") (pinfunction "A2N_L4") (pintype "output"))
    )
    (net (code "47") (name "unconnected-(U1D-A3-PadK1)") (class "Default")
      (node (ref "U1") (pin "K1") (pinfunction "A3_K1") (pintype "output"))
    )
    (net (code "48") (name "unconnected-(U1D-A3N-PadK2)") (class "Default")
      (node (ref "U1") (pin "K2") (pinfunction "A3N_K2") (pintype "output"))
    )
    (net (code "49") (name "unconnected-(U1D-A4-PadK3)") (class "Default")
      (node (ref "U1") (pin "K3") (pinfunction "A4_K3") (pintype "output"))
    )
    (net (code "50") (name "unconnected-(U1D-A4N-PadK4)") (class "Default")
      (node (ref "U1") (pin "K4") (pinfunction "A4N_K4") (pintype "output"))
    )
    (net (code "51") (name "unconnected-(U1D-A5-PadJ1)") (class "Default")
      (node (ref "U1") (pin "J1") (pinfunction "A5_J1") (pintype "output"))
    )
    (net (code "52") (name "unconnected-(U1D-A5N-PadJ2)") (class "Default")
      (node (ref "U1") (pin "J2") (pinfunction "A5N_J2") (pintype "output"))
    )
    (net (code "53") (name "unconnected-(U1D-A6-PadJ3)") (class "Default")
      (node (ref "U1") (pin "J3") (pinfunction "A6_J3") (pintype "output"))
    )
    (net (code "54") (name "unconnected-(U1D-A6N-PadJ4)") (class "Default")
      (node (ref "U1") (pin "J4") (pinfunction "A6N_J4") (pintype "output"))
    )
    (net (code "55") (name "unconnected-(U1D-A7-PadH1)") (class "Default")
      (node (ref "U1") (pin "H1") (pinfunction "A7_H1") (pintype "output"))
    )
    (net (code "56") (name "unconnected-(U1D-A7N-PadH2)") (class "Default")
      (node (ref "U1") (pin "H2") (pinfunction "A7N_H2") (pintype "output"))
    )
    (net (code "57") (name "unconnected-(U1D-A8-PadA3)") (class "Default")
      (node (ref "U1") (pin "A3") (pinfunction "A8_A3") (pintype "output"))
    )
    (net (code "58") (name "unconnected-(U1D-A8N-PadB3)") (class "Default")
      (node (ref "U1") (pin "B3") (pinfunction "A8N_B3") (pintype "output"))
    )
    (net (code "59") (name "unconnected-(U1D-A9-PadA4)") (class "Default")
      (node (ref "U1") (pin "A4") (pinfunction "A9_A4") (pintype "output"))
    )
    (net (code "60") (name "unconnected-(U1D-A9N-PadB4)") (class "Default")
      (node (ref "U1") (pin "B4") (pinfunction "A9N_B4") (pintype "output"))
    )
    (net (code "61") (name "unconnected-(U1D-ADR-PadM1)") (class "Default")
      (node (ref "U1") (pin "M1") (pinfunction "ADR_M1") (pintype "output"))
    )
    (net (code "62") (name "unconnected-(U1D-ADRN-PadM2)") (class "Default")
      (node (ref "U1") (pin "M2") (pinfunction "ADRN_M2") (pintype "output"))
    )
    (net (code "63") (name "unconnected-(U1D-AOR-PadA5)") (class "Default")
      (node (ref "U1") (pin "A5") (pinfunction "AOR_A5") (pintype "output"))
    )
    (net (code "64") (name "unconnected-(U1D-AORN-PadB5)") (class "Default")
      (node (ref "U1") (pin "B5") (pinfunction "AORN_B5") (pintype "output"))
    )
    (net (code "65") (name "unconnected-(U1E-B0-PadN3)") (class "Default")
      (node (ref "U1") (pin "N3") (pinfunction "B0_N3") (pintype "output"))
    )
    (net (code "66") (name "unconnected-(U1E-B0N-PadN4)") (class "Default")
      (node (ref "U1") (pin "N4") (pinfunction "B0N_N4") (pintype "output"))
    )
    (net (code "67") (name "unconnected-(U1E-B1-PadP1)") (class "Default")
      (node (ref "U1") (pin "P1") (pinfunction "B1_P1") (pintype "output"))
    )
    (net (code "68") (name "unconnected-(U1E-B1N-PadP2)") (class "Default")
      (node (ref "U1") (pin "P2") (pinfunction "B1N_P2") (pintype "output"))
    )
    (net (code "69") (name "unconnected-(U1E-B2-PadP3)") (class "Default")
      (node (ref "U1") (pin "P3") (pinfunction "B2_P3") (pintype "output"))
    )
    (net (code "70") (name "unconnected-(U1E-B2N-PadP4)") (class "Default")
      (node (ref "U1") (pin "P4") (pinfunction "B2N_P4") (pintype "output"))
    )
    (net (code "71") (name "unconnected-(U1E-B3-PadR1)") (class "Default")
      (node (ref "U1") (pin "R1") (pinfunction "B3_R1") (pintype "output"))
    )
    (net (code "72") (name "unconnected-(U1E-B3N-PadR2)") (class "Default")
      (node (ref "U1") (pin "R2") (pinfunction "B3N_R2") (pintype "output"))
    )
    (net (code "73") (name "unconnected-(U1E-B4-PadR3)") (class "Default")
      (node (ref "U1") (pin "R3") (pinfunction "B4_R3") (pintype "output"))
    )
    (net (code "74") (name "unconnected-(U1E-B4N-PadR4)") (class "Default")
      (node (ref "U1") (pin "R4") (pinfunction "B4N_R4") (pintype "output"))
    )
    (net (code "75") (name "unconnected-(U1E-B5-PadT1)") (class "Default")
      (node (ref "U1") (pin "T1") (pinfunction "B5_T1") (pintype "output"))
    )
    (net (code "76") (name "unconnected-(U1E-B5N-PadT2)") (class "Default")
      (node (ref "U1") (pin "T2") (pinfunction "B5N_T2") (pintype "output"))
    )
    (net (code "77") (name "unconnected-(U1E-B6-PadT3)") (class "Default")
      (node (ref "U1") (pin "T3") (pinfunction "B6_T3") (pintype "output"))
    )
    (net (code "78") (name "unconnected-(U1E-B6N-PadT4)") (class "Default")
      (node (ref "U1") (pin "T4") (pinfunction "B6N_T4") (pintype "output"))
    )
    (net (code "79") (name "unconnected-(U1E-B7-PadU1)") (class "Default")
      (node (ref "U1") (pin "U1") (pinfunction "B7_U1") (pintype "output"))
    )
    (net (code "80") (name "unconnected-(U1E-B7N-PadU2)") (class "Default")
      (node (ref "U1") (pin "U2") (pinfunction "B7N_U2") (pintype "output"))
    )
    (net (code "81") (name "unconnected-(U1E-B8-PadAD3)") (class "Default")
      (node (ref "U1") (pin "AD3") (pinfunction "B8_AD3") (pintype "output"))
    )
    (net (code "82") (name "unconnected-(U1E-B8N-PadAC3)") (class "Default")
      (node (ref "U1") (pin "AC3") (pinfunction "B8N_AC3") (pintype "output"))
    )
    (net (code "83") (name "unconnected-(U1E-B9-PadAD4)") (class "Default")
      (node (ref "U1") (pin "AD4") (pinfunction "B9_AD4") (pintype "output"))
    )
    (net (code "84") (name "unconnected-(U1E-B9N-PadAC4)") (class "Default")
      (node (ref "U1") (pin "AC4") (pinfunction "B9N_AC4") (pintype "output"))
    )
    (net (code "85") (name "unconnected-(U1E-BDR-PadN1)") (class "Default")
      (node (ref "U1") (pin "N1") (pinfunction "BDR_N1") (pintype "output"))
    )
    (net (code "86") (name "unconnected-(U1E-BDRN-PadN2)") (class "Default")
      (node (ref "U1") (pin "N2") (pinfunction "BDRN_N2") (pintype "output"))
    )
    (net (code "87") (name "unconnected-(U1E-BOR-PadAD5)") (class "Default")
      (node (ref "U1") (pin "AD5") (pinfunction "BOR_AD5") (pintype "output"))
    )
    (net (code "88") (name "unconnected-(U1E-BORN-PadAC5)") (class "Default")
      (node (ref "U1") (pin "AC5") (pinfunction "BORN_AC5") (pintype "output"))
    )
    (net (code "89") (name "unconnected-(U1F-C0-PadN22)") (class "Default")
      (node (ref "U1") (pin "N22") (pinfunction "C0_N22") (pintype "output"))
    )
    (net (code "90") (name "unconnected-(U1F-C0N-PadN21)") (class "Default")
      (node (ref "U1") (pin "N21") (pinfunction "C0N_N21") (pintype "output"))
    )
    (net (code "91") (name "unconnected-(U1F-C1-PadP24)") (class "Default")
      (node (ref "U1") (pin "P24") (pinfunction "C1_P24") (pintype "output"))
    )
    (net (code "92") (name "unconnected-(U1F-C1N-PadP23)") (class "Default")
      (node (ref "U1") (pin "P23") (pinfunction "C1N_P23") (pintype "output"))
    )
    (net (code "93") (name "unconnected-(U1F-C2-PadP22)") (class "Default")
      (node (ref "U1") (pin "P22") (pinfunction "C2_P22") (pintype "output"))
    )
    (net (code "94") (name "unconnected-(U1F-C2N-PadP21)") (class "Default")
      (node (ref "U1") (pin "P21") (pinfunction "C2N_P21") (pintype "output"))
    )
    (net (code "95") (name "unconnected-(U1F-C3-PadR24)") (class "Default")
      (node (ref "U1") (pin "R24") (pinfunction "C3_R24") (pintype "output"))
    )
    (net (code "96") (name "unconnected-(U1F-C3N-PadR23)") (class "Default")
      (node (ref "U1") (pin "R23") (pinfunction "C3N_R23") (pintype "output"))
    )
    (net (code "97") (name "unconnected-(U1F-C4-PadR22)") (class "Default")
      (node (ref "U1") (pin "R22") (pinfunction "C4_R22") (pintype "output"))
    )
    (net (code "98") (name "unconnected-(U1F-C4N-PadR21)") (class "Default")
      (node (ref "U1") (pin "R21") (pinfunction "C4N_R21") (pintype "output"))
    )
    (net (code "99") (name "unconnected-(U1F-C5-PadT24)") (class "Default")
      (node (ref "U1") (pin "T24") (pinfunction "C5_T24") (pintype "output"))
    )
    (net (code "100") (name "unconnected-(U1F-C5N-PadT23)") (class "Default")
      (node (ref "U1") (pin "T23") (pinfunction "C5N_T23") (pintype "output"))
    )
    (net (code "101") (name "unconnected-(U1F-C6-PadT22)") (class "Default")
      (node (ref "U1") (pin "T22") (pinfunction "C6_T22") (pintype "output"))
    )
    (net (code "102") (name "unconnected-(U1F-C6N-PadT21)") (class "Default")
      (node (ref "U1") (pin "T21") (pinfunction "C6N_T21") (pintype "output"))
    )
    (net (code "103") (name "unconnected-(U1F-C7-PadU24)") (class "Default")
      (node (ref "U1") (pin "U24") (pinfunction "C7_U24") (pintype "output"))
    )
    (net (code "104") (name "unconnected-(U1F-C7N-PadU23)") (class "Default")
      (node (ref "U1") (pin "U23") (pinfunction "C7N_U23") (pintype "output"))
    )
    (net (code "105") (name "unconnected-(U1F-C8-PadAD22)") (class "Default")
      (node (ref "U1") (pin "AD22") (pinfunction "C8_AD22") (pintype "output"))
    )
    (net (code "106") (name "unconnected-(U1F-C8N-PadAC22)") (class "Default")
      (node (ref "U1") (pin "AC22") (pinfunction "C8N_AC22") (pintype "output"))
    )
    (net (code "107") (name "unconnected-(U1F-C9-PadAD21)") (class "Default")
      (node (ref "U1") (pin "AD21") (pinfunction "C9_AD21") (pintype "output"))
    )
    (net (code "108") (name "unconnected-(U1F-C9N-PadAC21)") (class "Default")
      (node (ref "U1") (pin "AC21") (pinfunction "C9N_AC21") (pintype "output"))
    )
    (net (code "109") (name "unconnected-(U1F-CDR-PadN24)") (class "Default")
      (node (ref "U1") (pin "N24") (pinfunction "CDR_N24") (pintype "output"))
    )
    (net (code "110") (name "unconnected-(U1F-CDRN-PadN23)") (class "Default")
      (node (ref "U1") (pin "N23") (pinfunction "CDRN_N23") (pintype "output"))
    )
    (net (code "111") (name "unconnected-(U1F-COR-PadAD20)") (class "Default")
      (node (ref "U1") (pin "AD20") (pinfunction "COR_AD20") (pintype "output"))
    )
    (net (code "112") (name "unconnected-(U1F-CORN-PadAC20)") (class "Default")
      (node (ref "U1") (pin "AC20") (pinfunction "CORN_AC20") (pintype "output"))
    )
    (net (code "113") (name "unconnected-(U1G-D0-PadM22)") (class "Default")
      (node (ref "U1") (pin "M22") (pinfunction "D0_M22") (pintype "output"))
    )
    (net (code "114") (name "unconnected-(U1G-D0N-PadM21)") (class "Default")
      (node (ref "U1") (pin "M21") (pinfunction "D0N_M21") (pintype "output"))
    )
    (net (code "115") (name "unconnected-(U1G-D1-PadL24)") (class "Default")
      (node (ref "U1") (pin "L24") (pinfunction "D1_L24") (pintype "output"))
    )
    (net (code "116") (name "unconnected-(U1G-D1N-PadL23)") (class "Default")
      (node (ref "U1") (pin "L23") (pinfunction "D1N_L23") (pintype "output"))
    )
    (net (code "117") (name "unconnected-(U1G-D2-PadL22)") (class "Default")
      (node (ref "U1") (pin "L22") (pinfunction "D2_L22") (pintype "output"))
    )
    (net (code "118") (name "unconnected-(U1G-D2N-PadL21)") (class "Default")
      (node (ref "U1") (pin "L21") (pinfunction "D2N_L21") (pintype "output"))
    )
    (net (code "119") (name "unconnected-(U1G-D3-PadK24)") (class "Default")
      (node (ref "U1") (pin "K24") (pinfunction "D3_K24") (pintype "output"))
    )
    (net (code "120") (name "unconnected-(U1G-D3N-PadK23)") (class "Default")
      (node (ref "U1") (pin "K23") (pinfunction "D3N_K23") (pintype "output"))
    )
    (net (code "121") (name "unconnected-(U1G-D4-PadK22)") (class "Default")
      (node (ref "U1") (pin "K22") (pinfunction "D4_K22") (pintype "output"))
    )
    (net (code "122") (name "unconnected-(U1G-D4N-PadK21)") (class "Default")
      (node (ref "U1") (pin "K21") (pinfunction "D4N_K21") (pintype "output"))
    )
    (net (code "123") (name "unconnected-(U1G-D5-PadJ24)") (class "Default")
      (node (ref "U1") (pin "J24") (pinfunction "D5_J24") (pintype "output"))
    )
    (net (code "124") (name "unconnected-(U1G-D5N-PadJ23)") (class "Default")
      (node (ref "U1") (pin "J23") (pinfunction "D5N_J23") (pintype "output"))
    )
    (net (code "125") (name "unconnected-(U1G-D6-PadJ22)") (class "Default")
      (node (ref "U1") (pin "J22") (pinfunction "D6_J22") (pintype "output"))
    )
    (net (code "126") (name "unconnected-(U1G-D6N-PadJ21)") (class "Default")
      (node (ref "U1") (pin "J21") (pinfunction "D6N_J21") (pintype "output"))
    )
    (net (code "127") (name "unconnected-(U1G-D7-PadH24)") (class "Default")
      (node (ref "U1") (pin "H24") (pinfunction "D7_H24") (pintype "output"))
    )
    (net (code "128") (name "unconnected-(U1G-D7N-PadH23)") (class "Default")
      (node (ref "U1") (pin "H23") (pinfunction "D7N_H23") (pintype "output"))
    )
    (net (code "129") (name "unconnected-(U1G-D8-PadA22)") (class "Default")
      (node (ref "U1") (pin "A22") (pinfunction "D8_A22") (pintype "output"))
    )
    (net (code "130") (name "unconnected-(U1G-D8N-PadB22)") (class "Default")
      (node (ref "U1") (pin "B22") (pinfunction "D8N_B22") (pintype "output"))
    )
    (net (code "131") (name "unconnected-(U1G-D9-PadA21)") (class "Default")
      (node (ref "U1") (pin "A21") (pinfunction "D9_A21") (pintype "output"))
    )
    (net (code "132") (name "unconnected-(U1G-D9N-PadB21)") (class "Default")
      (node (ref "U1") (pin "B21") (pinfunction "D9N_B21") (pintype "output"))
    )
    (net (code "133") (name "unconnected-(U1G-DDR-PadM24)") (class "Default")
      (node (ref "U1") (pin "M24") (pinfunction "DDR_M24") (pintype "output"))
    )
    (net (code "134") (name "unconnected-(U1G-DDRN-PadM23)") (class "Default")
      (node (ref "U1") (pin "M23") (pinfunction "DDRN_M23") (pintype "output"))
    )
    (net (code "135") (name "unconnected-(U1G-DOR-PadA20)") (class "Default")
      (node (ref "U1") (pin "A20") (pinfunction "DOR_A20") (pintype "output"))
    )
    (net (code "136") (name "unconnected-(U1G-DORN-PadB20)") (class "Default")
      (node (ref "U1") (pin "B20") (pinfunction "DORN_B20") (pintype "output"))
    )
    (net (code "137") (name "unconnected-(U1H-CMIREFAB-PadB12)") (class "Default")
      (node (ref "U1") (pin "B12") (pinfunction "CMIREFAB_B12") (pintype "output"))
    )
    (net (code "138") (name "unconnected-(U1H-CMIREFCD-PadB13)") (class "Default")
      (node (ref "U1") (pin "B13") (pinfunction "CMIREFCD_B13") (pintype "output"))
    )
    (net (code "139") (name "unconnected-(U14A-1A-Pad2)") (class "Default")
      (node (ref "U14") (pin "2") (pinfunction "1A_2") (pintype "input"))
    )
    (net (code "140") (name "unconnected-(U14B-2A-Pad5)") (class "Default")
      (node (ref "U14") (pin "5") (pinfunction "2A_5") (pintype "input"))
    )
    (net (code "141") (name "unconnected-(U14C-3A-Pad9)") (class "Default")
      (node (ref "U14") (pin "9") (pinfunction "3A_9") (pintype "input"))
    )
    (net (code "142") (name "unconnected-(U14D-4A-Pad12)") (class "Default")
      (node (ref "U14") (pin "12") (pinfunction "4A_12") (pintype "input"))
    )
    (net (code "143") (name "unconnected-(U15-Y-Pad4)") (class "Default")
      (node (ref "U15") (pin "4") (pinfunction "Y_4") (pintype "output"))
    )
  )
)
